# ForceACQ.net
KiCad netlist of a schematic drawn in Altium Designer
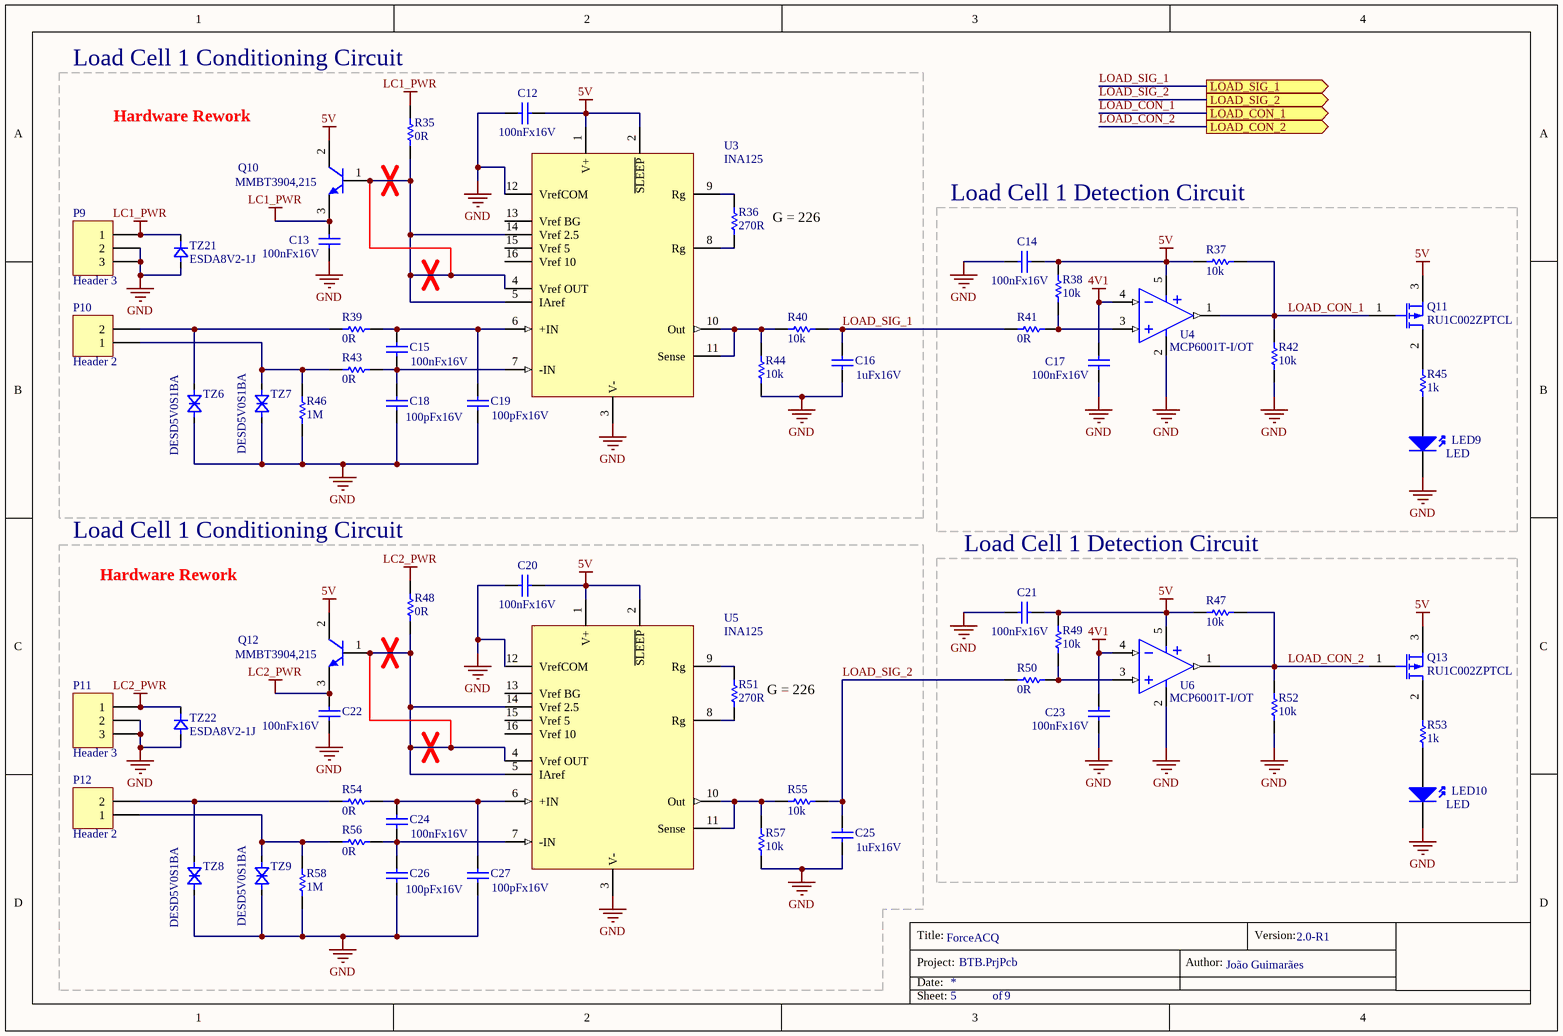
[diagram p0: ForceACQ.SchDoc]

(export (version "E")
  (design (tool "Eeschema 10.0.6"))
  (components
    (comp (ref "C12")
      (value "100nFx16V")
      (footprint "DISC-0805")
      (description "Capacitor")
      (libsource (lib "IntLib") (part "Cap"))
    )
    (comp (ref "C13")
      (value "100nFx16V")
      (footprint "DISC-0805")
      (description "Capacitor")
      (libsource (lib "IntLib") (part "Cap"))
    )
    (comp (ref "C14")
      (value "100nFx16V")
      (footprint "DISC-0805")
      (description "Capacitor")
      (libsource (lib "IntLib") (part "Cap"))
    )
    (comp (ref "C15")
      (value "100nFx16V")
      (footprint "DISC-0805")
      (description "Capacitor")
      (libsource (lib "IntLib") (part "Cap"))
    )
    (comp (ref "C16")
      (value "1uFx16V")
      (footprint "DISC-0805")
      (description "Capacitor")
      (libsource (lib "IntLib") (part "Cap"))
    )
    (comp (ref "C17")
      (value "100nFx16V")
      (footprint "DISC-0805")
      (description "Capacitor")
      (libsource (lib "IntLib") (part "Cap"))
    )
    (comp (ref "C18")
      (value "100pFx16V")
      (footprint "DISC-0805")
      (description "Capacitor")
      (libsource (lib "IntLib") (part "Cap"))
    )
    (comp (ref "C19")
      (value "100pFx16V")
      (footprint "DISC-0805")
      (description "Capacitor")
      (libsource (lib "IntLib") (part "Cap"))
    )
    (comp (ref "C20")
      (value "100nFx16V")
      (footprint "DISC-0805")
      (description "Capacitor")
      (libsource (lib "IntLib") (part "Cap"))
    )
    (comp (ref "C21")
      (value "100nFx16V")
      (footprint "DISC-0805")
      (description "Capacitor")
      (libsource (lib "IntLib") (part "Cap"))
    )
    (comp (ref "C22")
      (value "100nFx16V")
      (footprint "DISC-0805")
      (description "Capacitor")
      (libsource (lib "IntLib") (part "Cap"))
    )
    (comp (ref "C23")
      (value "100nFx16V")
      (footprint "DISC-0805")
      (description "Capacitor")
      (libsource (lib "IntLib") (part "Cap"))
    )
    (comp (ref "C24")
      (value "100nFx16V")
      (footprint "DISC-0805")
      (description "Capacitor")
      (libsource (lib "IntLib") (part "Cap"))
    )
    (comp (ref "C25")
      (value "1uFx16V")
      (footprint "DISC-0805")
      (description "Capacitor")
      (libsource (lib "IntLib") (part "Cap"))
    )
    (comp (ref "C26")
      (value "100pFx16V")
      (footprint "DISC-0805")
      (description "Capacitor")
      (libsource (lib "IntLib") (part "Cap"))
    )
    (comp (ref "C27")
      (value "100pFx16V")
      (footprint "DISC-0805")
      (description "Capacitor")
      (libsource (lib "IntLib") (part "Cap"))
    )
    (comp (ref "LED9") (value "LED") (footprint "DISC-LED-0.1-PTH") (libsource (lib "IntLib") (part "LED")))
    (comp (ref "LED10") (value "LED") (footprint "DISC-LED-0.1-PTH") (libsource (lib "IntLib") (part "LED")))
    (comp (ref "P9")
      (value "Header 3")
      (footprint "CON-FLEXWIRE-0.5MM2-1X3")
      (description "Header, 3-Pin")
      (fields (field (name "PUBLISHER") "Altium Limited"))
      (libsource (lib "IntLib") (part "Header 3"))
    )
    (comp (ref "P10")
      (value "Header 2")
      (footprint "CON-FLEXWIRE-0.5MM2-1X2")
      (description "Header, 2-Pin")
      (fields (field (name "PUBLISHER") "Altium Limited"))
      (libsource (lib "IntLib") (part "Header 2"))
    )
    (comp (ref "P11")
      (value "Header 3")
      (footprint "CON-FLEXWIRE-0.5MM2-1X3")
      (description "Header, 3-Pin")
      (fields (field (name "PUBLISHER") "Altium Limited"))
      (libsource (lib "IntLib") (part "Header 3"))
    )
    (comp (ref "P12")
      (value "Header 2")
      (footprint "CON-FLEXWIRE-0.5MM2-1X2")
      (description "Header, 2-Pin")
      (fields (field (name "PUBLISHER") "Altium Limited"))
      (libsource (lib "IntLib") (part "Header 2"))
    )
    (comp (ref "Q10")
      (value "MMBT3904,215")
      (footprint "DISC-SOT-23")
      (description "NPN Bipolar Transistor")
      (fields (field (name "PUBLISHER") "Altium Limited"))
      (libsource (lib "IntLib") (part "Transistor-NPN"))
    )
    (comp (ref "Q11")
      (value "RU1C002ZPTCL")
      (footprint "DISC-SOT-23")
      (description "P-Channel MOSFET")
      (libsource (lib "IntLib") (part "Transistor-PMOS"))
    )
    (comp (ref "Q12")
      (value "MMBT3904,215")
      (footprint "DISC-SOT-23")
      (description "NPN Bipolar Transistor")
      (fields (field (name "PUBLISHER") "Altium Limited"))
      (libsource (lib "IntLib") (part "Transistor-NPN"))
    )
    (comp (ref "Q13")
      (value "RU1C002ZPTCL")
      (footprint "DISC-SOT-23")
      (description "P-Channel MOSFET")
      (libsource (lib "IntLib") (part "Transistor-PMOS"))
    )
    (comp (ref "R35")
      (value "0R")
      (footprint "DISC-0805")
      (description "Resistor")
      (libsource (lib "IntLib") (part "Res"))
    )
    (comp (ref "R36")
      (value "270R")
      (footprint "DISC-0805")
      (description "Resistor")
      (libsource (lib "IntLib") (part "Res"))
    )
    (comp (ref "R37")
      (value "10k")
      (footprint "DISC-0805")
      (description "Resistor")
      (libsource (lib "IntLib") (part "Res"))
    )
    (comp (ref "R38")
      (value "10k")
      (footprint "DISC-0805")
      (description "Resistor")
      (libsource (lib "IntLib") (part "Res"))
    )
    (comp (ref "R39")
      (value "0R")
      (footprint "DISC-0805")
      (description "Resistor")
      (libsource (lib "IntLib") (part "Res"))
    )
    (comp (ref "R40")
      (value "10k")
      (footprint "DISC-0805")
      (description "Resistor")
      (libsource (lib "IntLib") (part "Res"))
    )
    (comp (ref "R41")
      (value "0R")
      (footprint "DISC-0805")
      (description "Resistor")
      (libsource (lib "IntLib") (part "Res"))
    )
    (comp (ref "R42")
      (value "10k")
      (footprint "DISC-0805")
      (description "Resistor")
      (libsource (lib "IntLib") (part "Res"))
    )
    (comp (ref "R43")
      (value "0R")
      (footprint "DISC-0805")
      (description "Resistor")
      (libsource (lib "IntLib") (part "Res"))
    )
    (comp (ref "R44")
      (value "10k")
      (footprint "DISC-0805")
      (description "Resistor")
      (libsource (lib "IntLib") (part "Res"))
    )
    (comp (ref "R45")
      (value "1k")
      (footprint "DISC-0805")
      (description "Resistor")
      (libsource (lib "IntLib") (part "Res"))
    )
    (comp (ref "R46")
      (value "1M")
      (footprint "DISC-0805")
      (description "Resistor")
      (libsource (lib "IntLib") (part "Res"))
    )
    (comp (ref "R47")
      (value "10k")
      (footprint "DISC-0805")
      (description "Resistor")
      (libsource (lib "IntLib") (part "Res"))
    )
    (comp (ref "R48")
      (value "0R")
      (footprint "DISC-0805")
      (description "Resistor")
      (libsource (lib "IntLib") (part "Res"))
    )
    (comp (ref "R49")
      (value "10k")
      (footprint "DISC-0805")
      (description "Resistor")
      (libsource (lib "IntLib") (part "Res"))
    )
    (comp (ref "R50")
      (value "0R")
      (footprint "DISC-0805")
      (description "Resistor")
      (libsource (lib "IntLib") (part "Res"))
    )
    (comp (ref "R51")
      (value "270R")
      (footprint "DISC-0805")
      (description "Resistor")
      (libsource (lib "IntLib") (part "Res"))
    )
    (comp (ref "R52")
      (value "10k")
      (footprint "DISC-0805")
      (description "Resistor")
      (libsource (lib "IntLib") (part "Res"))
    )
    (comp (ref "R53")
      (value "1k")
      (footprint "DISC-0805")
      (description "Resistor")
      (libsource (lib "IntLib") (part "Res"))
    )
    (comp (ref "R54")
      (value "0R")
      (footprint "DISC-0805")
      (description "Resistor")
      (libsource (lib "IntLib") (part "Res"))
    )
    (comp (ref "R55")
      (value "10k")
      (footprint "DISC-0805")
      (description "Resistor")
      (libsource (lib "IntLib") (part "Res"))
    )
    (comp (ref "R56")
      (value "0R")
      (footprint "DISC-0805")
      (description "Resistor")
      (libsource (lib "IntLib") (part "Res"))
    )
    (comp (ref "R57")
      (value "10k")
      (footprint "DISC-0805")
      (description "Resistor")
      (libsource (lib "IntLib") (part "Res"))
    )
    (comp (ref "R58")
      (value "1M")
      (footprint "DISC-0805")
      (description "Resistor")
      (libsource (lib "IntLib") (part "Res"))
    )
    (comp (ref "TZ6")
      (value "DESD5V0S1BA")
      (footprint "DISC-SOD-323")
      (description "TVZ-Bi-Directional")
      (libsource (lib "IntLib") (part "TVZ-Bi-Directional"))
    )
    (comp (ref "TZ7")
      (value "DESD5V0S1BA")
      (footprint "DISC-SOD-323")
      (description "TVZ-Bi-Directional")
      (libsource (lib "IntLib") (part "TVZ-Bi-Directional"))
    )
    (comp (ref "TZ8")
      (value "DESD5V0S1BA")
      (footprint "DISC-SOD-323")
      (description "TVZ-Bi-Directional")
      (libsource (lib "IntLib") (part "TVZ-Bi-Directional"))
    )
    (comp (ref "TZ9")
      (value "DESD5V0S1BA")
      (footprint "DISC-SOD-323")
      (description "TVZ-Bi-Directional")
      (libsource (lib "IntLib") (part "TVZ-Bi-Directional"))
    )
    (comp (ref "TZ21")
      (value "ESDA8V2-1J")
      (footprint "DISC-SOD-323")
      (description "TVZ-Unidirectional")
      (libsource (lib "IntLib") (part "TVZ-Unidirectional"))
    )
    (comp (ref "TZ22")
      (value "ESDA8V2-1J")
      (footprint "DISC-SOD-323")
      (description "TVZ-Unidirectional")
      (libsource (lib "IntLib") (part "TVZ-Unidirectional"))
    )
    (comp (ref "U3")
      (value "INA125")
      (footprint "CI-SOIC-16")
      (description "INSTRUMENTATION AMPLIFIER With Precision Voltage Reference")
      (libsource (lib "IntLib") (part "INA125P"))
    )
    (comp (ref "U4")
      (value "MCP6001T-I/OT")
      (footprint "CI-SOT-23-5")
      (description "Operational Amplifiers - Op Amps Single 1.8V 1MHz")
      (libsource (lib "IntLib") (part "MCP6001T-I/OT"))
    )
    (comp (ref "U5")
      (value "INA125")
      (footprint "CI-SOIC-16")
      (description "INSTRUMENTATION AMPLIFIER With Precision Voltage Reference")
      (libsource (lib "IntLib") (part "INA125P"))
    )
    (comp (ref "U6")
      (value "MCP6001T-I/OT")
      (footprint "CI-SOT-23-5")
      (description "Operational Amplifiers - Op Amps Single 1.8V 1MHz")
      (libsource (lib "IntLib") (part "MCP6001T-I/OT"))
    )
  )
  (nets
    (net (code "1") (name "/LOAD_CON_1") (class "Default")
      (node (ref "Q11") (pin "1") (pinfunction "G_1") (pintype "passive"))
      (node (ref "R37") (pin "2") (pinfunction "2_2") (pintype "passive"))
      (node (ref "R42") (pin "1") (pinfunction "1_1") (pintype "passive"))
      (node (ref "U4") (pin "1") (pinfunction "Out_1") (pintype "output"))
    )
    (net (code "2") (name "/LOAD_CON_2") (class "Default")
      (node (ref "Q13") (pin "1") (pinfunction "G_1") (pintype "passive"))
      (node (ref "R47") (pin "2") (pinfunction "2_2") (pintype "passive"))
      (node (ref "R52") (pin "1") (pinfunction "1_1") (pintype "passive"))
      (node (ref "U6") (pin "1") (pinfunction "Out_1") (pintype "output"))
    )
    (net (code "3") (name "/LOAD_SIG_1") (class "Default")
      (node (ref "C16") (pin "2") (pinfunction "2_2") (pintype "passive"))
      (node (ref "R40") (pin "2") (pinfunction "2_2") (pintype "passive"))
      (node (ref "R41") (pin "1") (pinfunction "1_1") (pintype "passive"))
    )
    (net (code "4") (name "/LOAD_SIG_2") (class "Default")
      (node (ref "C25") (pin "2") (pinfunction "2_2") (pintype "passive"))
      (node (ref "R50") (pin "1") (pinfunction "1_1") (pintype "passive"))
      (node (ref "R55") (pin "2") (pinfunction "2_2") (pintype "passive"))
    )
    (net (code "5") (name "4V1") (class "Default")
      (node (ref "C17") (pin "2") (pinfunction "2_2") (pintype "passive"))
      (node (ref "C23") (pin "2") (pinfunction "2_2") (pintype "passive"))
      (node (ref "U4") (pin "4") (pinfunction "IN-_4") (pintype "input"))
      (node (ref "U6") (pin "4") (pinfunction "IN-_4") (pintype "input"))
    )
    (net (code "6") (name "5V") (class "Default")
      (node (ref "C12") (pin "1") (pinfunction "1_1") (pintype "passive"))
      (node (ref "C14") (pin "2") (pinfunction "2_2") (pintype "passive"))
      (node (ref "C20") (pin "1") (pinfunction "1_1") (pintype "passive"))
      (node (ref "C21") (pin "2") (pinfunction "2_2") (pintype "passive"))
      (node (ref "Q10") (pin "2") (pinfunction "C_2") (pintype "passive"))
      (node (ref "Q11") (pin "3") (pinfunction "S_3") (pintype "passive"))
      (node (ref "Q12") (pin "2") (pinfunction "C_2") (pintype "passive"))
      (node (ref "Q13") (pin "3") (pinfunction "S_3") (pintype "passive"))
      (node (ref "R37") (pin "1") (pinfunction "1_1") (pintype "passive"))
      (node (ref "R38") (pin "1") (pinfunction "1_1") (pintype "passive"))
      (node (ref "R47") (pin "1") (pinfunction "1_1") (pintype "passive"))
      (node (ref "R49") (pin "1") (pinfunction "1_1") (pintype "passive"))
      (node (ref "U3") (pin "1") (pinfunction "V+_1") (pintype "power_in"))
      (node (ref "U3") (pin "2") (pinfunction "~{SLEEP}_2") (pintype "passive"))
      (node (ref "U4") (pin "5") (pinfunction "V+_5") (pintype "power_in"))
      (node (ref "U5") (pin "1") (pinfunction "V+_1") (pintype "power_in"))
      (node (ref "U5") (pin "2") (pinfunction "~{SLEEP}_2") (pintype "passive"))
      (node (ref "U6") (pin "5") (pinfunction "V+_5") (pintype "power_in"))
    )
    (net (code "7") (name "GND") (class "Default")
      (node (ref "C12") (pin "2") (pinfunction "2_2") (pintype "passive"))
      (node (ref "C13") (pin "1") (pinfunction "1_1") (pintype "passive"))
      (node (ref "C14") (pin "1") (pinfunction "1_1") (pintype "passive"))
      (node (ref "C16") (pin "1") (pinfunction "1_1") (pintype "passive"))
      (node (ref "C17") (pin "1") (pinfunction "1_1") (pintype "passive"))
      (node (ref "C18") (pin "1") (pinfunction "1_1") (pintype "passive"))
      (node (ref "C19") (pin "1") (pinfunction "1_1") (pintype "passive"))
      (node (ref "C20") (pin "2") (pinfunction "2_2") (pintype "passive"))
      (node (ref "C21") (pin "1") (pinfunction "1_1") (pintype "passive"))
      (node (ref "C22") (pin "1") (pinfunction "1_1") (pintype "passive"))
      (node (ref "C23") (pin "1") (pinfunction "1_1") (pintype "passive"))
      (node (ref "C25") (pin "1") (pinfunction "1_1") (pintype "passive"))
      (node (ref "C26") (pin "1") (pinfunction "1_1") (pintype "passive"))
      (node (ref "C27") (pin "1") (pinfunction "1_1") (pintype "passive"))
      (node (ref "LED10") (pin "2") (pinfunction "K_2") (pintype "passive"))
      (node (ref "LED9") (pin "2") (pinfunction "K_2") (pintype "passive"))
      (node (ref "P11") (pin "2") (pinfunction "2_2") (pintype "passive"))
      (node (ref "P11") (pin "3") (pinfunction "3_3") (pintype "passive"))
      (node (ref "P9") (pin "2") (pinfunction "2_2") (pintype "passive"))
      (node (ref "P9") (pin "3") (pinfunction "3_3") (pintype "passive"))
      (node (ref "R42") (pin "2") (pinfunction "2_2") (pintype "passive"))
      (node (ref "R44") (pin "2") (pinfunction "2_2") (pintype "passive"))
      (node (ref "R46") (pin "1") (pinfunction "1_1") (pintype "passive"))
      (node (ref "R52") (pin "2") (pinfunction "2_2") (pintype "passive"))
      (node (ref "R57") (pin "2") (pinfunction "2_2") (pintype "passive"))
      (node (ref "R58") (pin "1") (pinfunction "1_1") (pintype "passive"))
      (node (ref "TZ21") (pin "1") (pinfunction "A_1") (pintype "passive"))
      (node (ref "TZ22") (pin "1") (pinfunction "A_1") (pintype "passive"))
      (node (ref "TZ6") (pin "1") (pinfunction "A_1") (pintype "passive"))
      (node (ref "TZ7") (pin "1") (pinfunction "A_1") (pintype "passive"))
      (node (ref "TZ8") (pin "1") (pinfunction "A_1") (pintype "passive"))
      (node (ref "TZ9") (pin "1") (pinfunction "A_1") (pintype "passive"))
      (node (ref "U3") (pin "12") (pinfunction "VrefCOM_12") (pintype "passive"))
      (node (ref "U3") (pin "3") (pinfunction "V-_3") (pintype "power_in"))
      (node (ref "U4") (pin "2") (pinfunction "V-_2") (pintype "power_in"))
      (node (ref "U5") (pin "12") (pinfunction "VrefCOM_12") (pintype "passive"))
      (node (ref "U5") (pin "3") (pinfunction "V-_3") (pintype "power_in"))
      (node (ref "U6") (pin "2") (pinfunction "V-_2") (pintype "power_in"))
    )
    (net (code "8") (name "LC1_PWR") (class "Default")
      (node (ref "C13") (pin "2") (pinfunction "2_2") (pintype "passive"))
      (node (ref "P9") (pin "1") (pinfunction "1_1") (pintype "passive"))
      (node (ref "Q10") (pin "3") (pinfunction "E_3") (pintype "passive"))
      (node (ref "R35") (pin "1") (pinfunction "1_1") (pintype "passive"))
      (node (ref "TZ21") (pin "2") (pinfunction "C_2") (pintype "passive"))
    )
    (net (code "9") (name "LC2_PWR") (class "Default")
      (node (ref "C22") (pin "2") (pinfunction "2_2") (pintype "passive"))
      (node (ref "P11") (pin "1") (pinfunction "1_1") (pintype "passive"))
      (node (ref "Q12") (pin "3") (pinfunction "E_3") (pintype "passive"))
      (node (ref "R48") (pin "1") (pinfunction "1_1") (pintype "passive"))
      (node (ref "TZ22") (pin "2") (pinfunction "C_2") (pintype "passive"))
    )
    (net (code "10") (name "Net-(LED9-A)") (class "Default")
      (node (ref "LED9") (pin "1") (pinfunction "A_1") (pintype "passive"))
      (node (ref "R45") (pin "1") (pinfunction "1_1") (pintype "passive"))
    )
    (net (code "11") (name "Net-(LED10-A)") (class "Default")
      (node (ref "LED10") (pin "1") (pinfunction "A_1") (pintype "passive"))
      (node (ref "R53") (pin "1") (pinfunction "1_1") (pintype "passive"))
    )
    (net (code "12") (name "Net-(Q10-B)") (class "Default")
      (node (ref "Q10") (pin "1") (pinfunction "B_1") (pintype "passive"))
      (node (ref "R35") (pin "2") (pinfunction "2_2") (pintype "passive"))
      (node (ref "U3") (pin "14") (pinfunction "Vref_2.5_14") (pintype "passive"))
      (node (ref "U3") (pin "4") (pinfunction "Vref_OUT_4") (pintype "passive"))
      (node (ref "U3") (pin "5") (pinfunction "IAref_5") (pintype "passive"))
    )
    (net (code "13") (name "Net-(Q11-D)") (class "Default")
      (node (ref "Q11") (pin "2") (pinfunction "D_2") (pintype "passive"))
      (node (ref "R45") (pin "2") (pinfunction "2_2") (pintype "passive"))
    )
    (net (code "14") (name "Net-(Q12-B)") (class "Default")
      (node (ref "Q12") (pin "1") (pinfunction "B_1") (pintype "passive"))
      (node (ref "R48") (pin "2") (pinfunction "2_2") (pintype "passive"))
      (node (ref "U5") (pin "14") (pinfunction "Vref_2.5_14") (pintype "passive"))
      (node (ref "U5") (pin "4") (pinfunction "Vref_OUT_4") (pintype "passive"))
      (node (ref "U5") (pin "5") (pinfunction "IAref_5") (pintype "passive"))
    )
    (net (code "15") (name "Net-(Q13-D)") (class "Default")
      (node (ref "Q13") (pin "2") (pinfunction "D_2") (pintype "passive"))
      (node (ref "R53") (pin "2") (pinfunction "2_2") (pintype "passive"))
    )
    (net (code "16") (name "Net-(R36-Pad1)") (class "Default")
      (node (ref "R36") (pin "1") (pinfunction "1_1") (pintype "passive"))
      (node (ref "U3") (pin "9") (pinfunction "Rg_9") (pintype "passive"))
    )
    (net (code "17") (name "Net-(R36-Pad2)") (class "Default")
      (node (ref "R36") (pin "2") (pinfunction "2_2") (pintype "passive"))
      (node (ref "U3") (pin "8") (pinfunction "Rg_8") (pintype "passive"))
    )
    (net (code "18") (name "Net-(R51-Pad1)") (class "Default")
      (node (ref "R51") (pin "1") (pinfunction "1_1") (pintype "passive"))
      (node (ref "U5") (pin "9") (pinfunction "Rg_9") (pintype "passive"))
    )
    (net (code "19") (name "Net-(R51-Pad2)") (class "Default")
      (node (ref "R51") (pin "2") (pinfunction "2_2") (pintype "passive"))
      (node (ref "U5") (pin "8") (pinfunction "Rg_8") (pintype "passive"))
    )
    (net (code "20") (name "Net-(TZ6-K)") (class "Default")
      (node (ref "P10") (pin "2") (pinfunction "2_2") (pintype "passive"))
      (node (ref "R39") (pin "2") (pinfunction "2_2") (pintype "passive"))
      (node (ref "TZ6") (pin "2") (pinfunction "K_2") (pintype "passive"))
    )
    (net (code "21") (name "Net-(TZ7-K)") (class "Default")
      (node (ref "P10") (pin "1") (pinfunction "1_1") (pintype "passive"))
      (node (ref "R43") (pin "2") (pinfunction "2_2") (pintype "passive"))
      (node (ref "R46") (pin "2") (pinfunction "2_2") (pintype "passive"))
      (node (ref "TZ7") (pin "2") (pinfunction "K_2") (pintype "passive"))
    )
    (net (code "22") (name "Net-(TZ8-K)") (class "Default")
      (node (ref "P12") (pin "2") (pinfunction "2_2") (pintype "passive"))
      (node (ref "R54") (pin "2") (pinfunction "2_2") (pintype "passive"))
      (node (ref "TZ8") (pin "2") (pinfunction "K_2") (pintype "passive"))
    )
    (net (code "23") (name "Net-(TZ9-K)") (class "Default")
      (node (ref "P12") (pin "1") (pinfunction "1_1") (pintype "passive"))
      (node (ref "R56") (pin "2") (pinfunction "2_2") (pintype "passive"))
      (node (ref "R58") (pin "2") (pinfunction "2_2") (pintype "passive"))
      (node (ref "TZ9") (pin "2") (pinfunction "K_2") (pintype "passive"))
    )
    (net (code "24") (name "Net-(U3-+IN)") (class "Default")
      (node (ref "C15") (pin "2") (pinfunction "2_2") (pintype "passive"))
      (node (ref "C19") (pin "2") (pinfunction "2_2") (pintype "passive"))
      (node (ref "R39") (pin "1") (pinfunction "1_1") (pintype "passive"))
      (node (ref "U3") (pin "6") (pinfunction "+IN_6") (pintype "input"))
    )
    (net (code "25") (name "Net-(U3--IN)") (class "Default")
      (node (ref "C15") (pin "1") (pinfunction "1_1") (pintype "passive"))
      (node (ref "C18") (pin "2") (pinfunction "2_2") (pintype "passive"))
      (node (ref "R43") (pin "1") (pinfunction "1_1") (pintype "passive"))
      (node (ref "U3") (pin "7") (pinfunction "-IN_7") (pintype "input"))
    )
    (net (code "26") (name "Net-(U3-Out)") (class "Default")
      (node (ref "R40") (pin "1") (pinfunction "1_1") (pintype "passive"))
      (node (ref "R44") (pin "1") (pinfunction "1_1") (pintype "passive"))
      (node (ref "U3") (pin "10") (pinfunction "Out_10") (pintype "output"))
      (node (ref "U3") (pin "11") (pinfunction "Sense_11") (pintype "passive"))
    )
    (net (code "27") (name "Net-(U4-IN+)") (class "Default")
      (node (ref "R38") (pin "2") (pinfunction "2_2") (pintype "passive"))
      (node (ref "R41") (pin "2") (pinfunction "2_2") (pintype "passive"))
      (node (ref "U4") (pin "3") (pinfunction "IN+_3") (pintype "input"))
    )
    (net (code "28") (name "Net-(U5-+IN)") (class "Default")
      (node (ref "C24") (pin "2") (pinfunction "2_2") (pintype "passive"))
      (node (ref "C27") (pin "2") (pinfunction "2_2") (pintype "passive"))
      (node (ref "R54") (pin "1") (pinfunction "1_1") (pintype "passive"))
      (node (ref "U5") (pin "6") (pinfunction "+IN_6") (pintype "input"))
    )
    (net (code "29") (name "Net-(U5--IN)") (class "Default")
      (node (ref "C24") (pin "1") (pinfunction "1_1") (pintype "passive"))
      (node (ref "C26") (pin "2") (pinfunction "2_2") (pintype "passive"))
      (node (ref "R56") (pin "1") (pinfunction "1_1") (pintype "passive"))
      (node (ref "U5") (pin "7") (pinfunction "-IN_7") (pintype "input"))
    )
    (net (code "30") (name "Net-(U5-Out)") (class "Default")
      (node (ref "R55") (pin "1") (pinfunction "1_1") (pintype "passive"))
      (node (ref "R57") (pin "1") (pinfunction "1_1") (pintype "passive"))
      (node (ref "U5") (pin "10") (pinfunction "Out_10") (pintype "output"))
      (node (ref "U5") (pin "11") (pinfunction "Sense_11") (pintype "passive"))
    )
    (net (code "31") (name "Net-(U6-IN+)") (class "Default")
      (node (ref "R49") (pin "2") (pinfunction "2_2") (pintype "passive"))
      (node (ref "R50") (pin "2") (pinfunction "2_2") (pintype "passive"))
      (node (ref "U6") (pin "3") (pinfunction "IN+_3") (pintype "input"))
    )
    (net (code "32") (name "unconnected-(U3-Vref_5-Pad15)") (class "Default")
      (node (ref "U3") (pin "15") (pinfunction "Vref_5_15") (pintype "passive"))
    )
    (net (code "33") (name "unconnected-(U3-Vref_10-Pad16)") (class "Default")
      (node (ref "U3") (pin "16") (pinfunction "Vref_10_16") (pintype "passive"))
    )
    (net (code "34") (name "unconnected-(U3-Vref_BG-Pad13)") (class "Default")
      (node (ref "U3") (pin "13") (pinfunction "Vref_BG_13") (pintype "passive"))
    )
    (net (code "35") (name "unconnected-(U5-Vref_5-Pad15)") (class "Default")
      (node (ref "U5") (pin "15") (pinfunction "Vref_5_15") (pintype "passive"))
    )
    (net (code "36") (name "unconnected-(U5-Vref_10-Pad16)") (class "Default")
      (node (ref "U5") (pin "16") (pinfunction "Vref_10_16") (pintype "passive"))
    )
    (net (code "37") (name "unconnected-(U5-Vref_BG-Pad13)") (class "Default")
      (node (ref "U5") (pin "13") (pinfunction "Vref_BG_13") (pintype "passive"))
    )
  )
)
